# MCU.net
KiCad netlist of a schematic drawn in Altium Designer
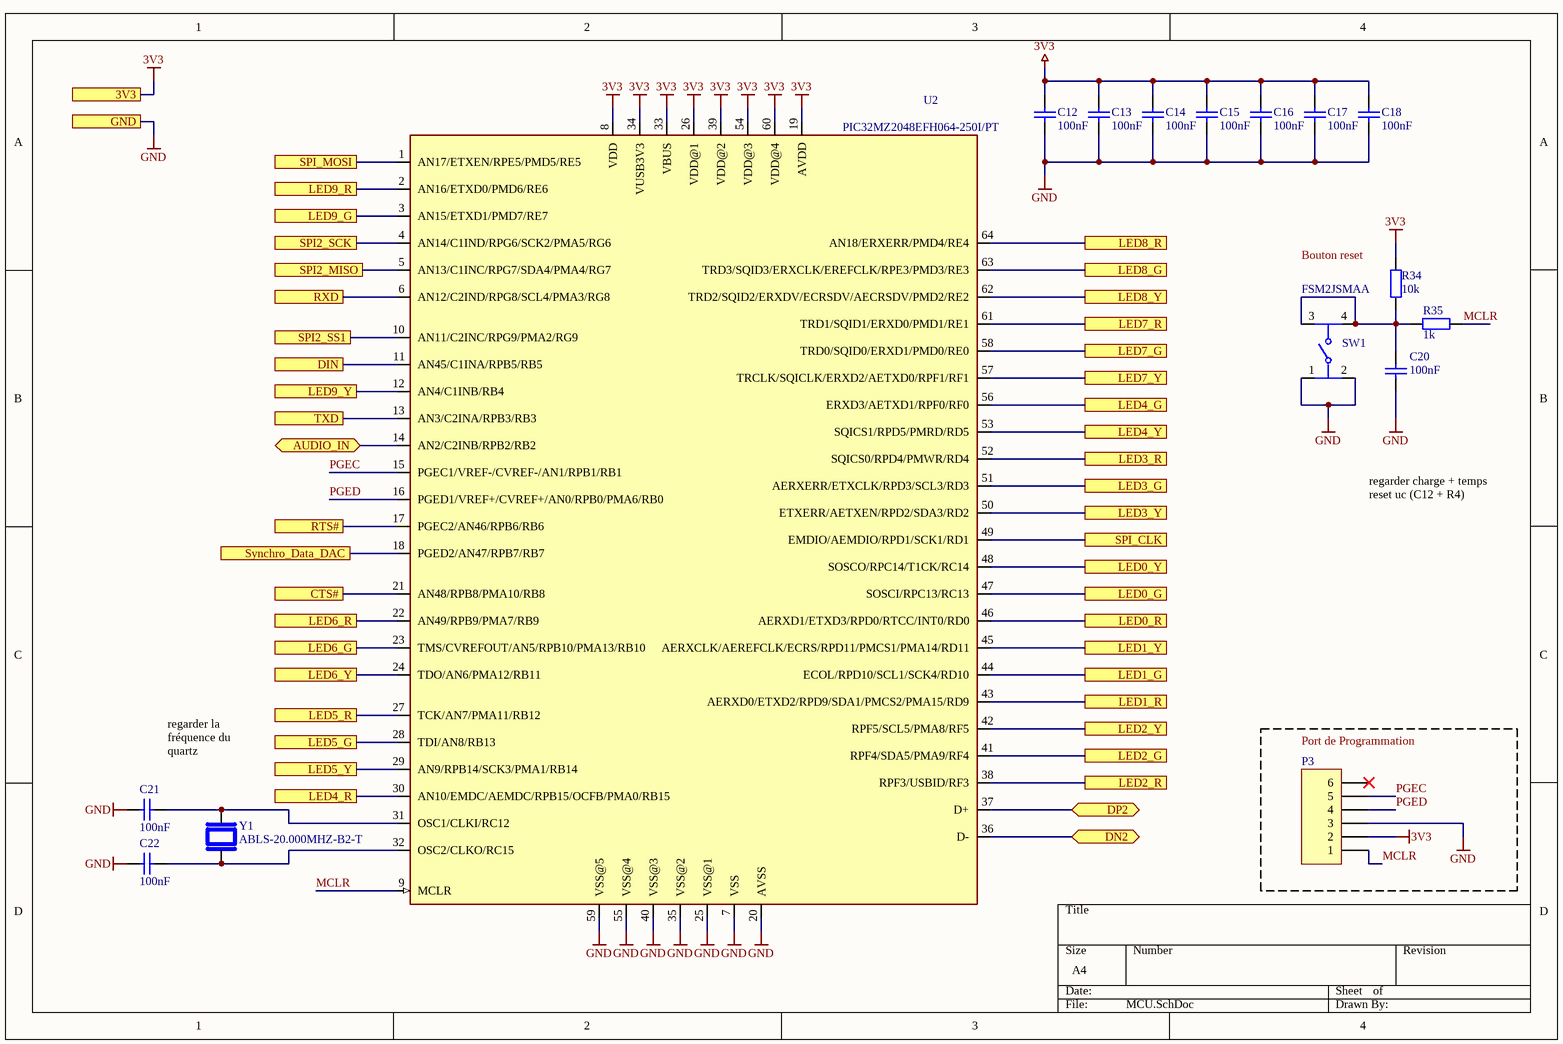
[diagram p0: MCU.SchDoc]

(export (version "E")
  (design (tool "Eeschema 10.0.6"))
  (components
    (comp (ref "C12")
      (value "100nF")
      (footprint "C0805")
      (description "Capacitor")
      (fields (field (name "PUBLISHER") "Altium Limited"))
      (libsource (lib "Miscellaneous Devices") (part "Cap"))
    )
    (comp (ref "C13")
      (value "100nF")
      (footprint "C0805")
      (description "Capacitor")
      (fields (field (name "PUBLISHER") "Altium Limited"))
      (libsource (lib "Miscellaneous Devices") (part "Cap"))
    )
    (comp (ref "C14")
      (value "100nF")
      (footprint "C0805")
      (description "Capacitor")
      (fields (field (name "PUBLISHER") "Altium Limited"))
      (libsource (lib "Miscellaneous Devices") (part "Cap"))
    )
    (comp (ref "C15")
      (value "100nF")
      (footprint "C0805")
      (description "Capacitor")
      (fields (field (name "PUBLISHER") "Altium Limited"))
      (libsource (lib "Miscellaneous Devices") (part "Cap"))
    )
    (comp (ref "C16")
      (value "100nF")
      (footprint "C0805")
      (description "Capacitor")
      (fields (field (name "PUBLISHER") "Altium Limited"))
      (libsource (lib "Miscellaneous Devices") (part "Cap"))
    )
    (comp (ref "C17")
      (value "100nF")
      (footprint "C0805")
      (description "Capacitor")
      (fields (field (name "PUBLISHER") "Altium Limited"))
      (libsource (lib "Miscellaneous Devices") (part "Cap"))
    )
    (comp (ref "C18")
      (value "100nF")
      (footprint "C0805")
      (description "Capacitor")
      (fields (field (name "PUBLISHER") "Altium Limited"))
      (libsource (lib "Miscellaneous Devices") (part "Cap"))
    )
    (comp (ref "C20")
      (value "100nF")
      (footprint "C0805")
      (description "10nf")
      (fields (field (name "PUBLISHER") "Altium Limited"))
      (libsource (lib "Miscellaneous Devices") (part "Cap"))
    )
    (comp (ref "C21")
      (value "100nF")
      (footprint "C0805")
      (description "10nf")
      (fields (field (name "PUBLISHER") "Altium Limited"))
      (libsource (lib "Miscellaneous Devices") (part "Cap"))
    )
    (comp (ref "C22")
      (value "100nF")
      (footprint "C0805")
      (description "10nf")
      (fields (field (name "PUBLISHER") "Altium Limited"))
      (libsource (lib "Miscellaneous Devices") (part "Cap"))
    )
    (comp (ref "P3")
      (value "76384-406LF")
      (footprint "HDR1X6")
      (description "Header, 6-Pin")
      (fields (field (name "PUBLISHER") "Altium Limited"))
      (libsource (lib "Miscellaneous Connectors") (part "Header 6"))
    )
    (comp (ref "R34")
      (value "10k")
      (footprint "RESC2012X06M")
      (description "Resistor")
      (fields (field (name "PUBLISHER") "Altium Limited"))
      (libsource (lib "") (part "Res2_1"))
    )
    (comp (ref "R35")
      (value "1k")
      (footprint "RESC2012X06M")
      (description "Resistor")
      (fields (field (name "PUBLISHER") "Altium Limited"))
      (libsource (lib "Miscellaneous Devices") (part "Res2"))
    )
    (comp (ref "SW1")
      (value "FSM2JSMAA")
      (footprint "FP-FSM2JSMAA-MFG")
      (description "SWITCH TACTILE SPST-NO 0.05A 24V")
      (fields
        (field (name "MANUFACTURER") "TE Connectivity")
        (field (name "OCTOPART") "https://octopart.com/fsm2jsmaa-te+connectivity-41720620")
      )
      (libsource (lib "Altium Content Vault") (part "b8895f3f4cefb76e1819d2863dba89b"))
    )
    (comp (ref "U2")
      (value "PIC32MZ2048EFH064-250I/PT")
      (footprint "QFP50P1200X1200X120-64N")
      (description "MIPS32Â® M-Class PICÂ® 32MZ Microcontroller IC 32-Bit 250MHz 2MB _2M x 8_ FLASH 64-TQFP _10x10_")
      (fields
        (field (name "MF") "Microchip")
        (field (name "DIGI-KEY_PART_NUMBER") "PIC32MZ2048EFH064-250I/PT-ND")
      )
      (libsource (lib "2225B_VumetreFrequenciel") (part "PIC32MZ2048EFH064-250I/PT"))
    )
    (comp (ref "Y1")
      (value "ABLS-20.000MHZ-B2-T")
      (footprint "XTAL_ABLS-20.000MHZ-B2-T")
      (description "HC/49US (AT49) SMD LOW PROFILE CRYSTAL")
      (fields (field (name "MF") "Abracon LLC"))
      (libsource (lib "2225B_VumetreFrequenciel") (part "ABLS-20.000MHZ-B2-T"))
    )
  )
  (nets
    (net (code "1") (name "/AUDIO_IN") (class "Default")
      (node (ref "U2") (pin "14") (pinfunction "AN2/C2INB/RPB2/RB2_14") (pintype "passive"))
    )
    (net (code "2") (name "/CTS#") (class "Default")
      (node (ref "U2") (pin "21") (pinfunction "AN48/RPB8/PMA10/RB8_21") (pintype "passive"))
    )
    (net (code "3") (name "/DIN") (class "Default")
      (node (ref "U2") (pin "11") (pinfunction "AN45/C1INA/RPB5/RB5_11") (pintype "passive"))
    )
    (net (code "4") (name "/DN2") (class "Default")
      (node (ref "U2") (pin "36") (pinfunction "D-_36") (pintype "passive"))
    )
    (net (code "5") (name "/DP2") (class "Default")
      (node (ref "U2") (pin "37") (pinfunction "D+_37") (pintype "passive"))
    )
    (net (code "6") (name "/LED0_G") (class "Default")
      (node (ref "U2") (pin "47") (pinfunction "SOSCI/RPC13/RC13_47") (pintype "passive"))
    )
    (net (code "7") (name "/LED0_R") (class "Default")
      (node (ref "U2") (pin "46") (pinfunction "AERXD1/ETXD3/RPD0/RTCC/INT0/RD0_46") (pintype "passive"))
    )
    (net (code "8") (name "/LED0_Y") (class "Default")
      (node (ref "U2") (pin "48") (pinfunction "SOSCO/RPC14/T1CK/RC14_48") (pintype "passive"))
    )
    (net (code "9") (name "/LED1_G") (class "Default")
      (node (ref "U2") (pin "44") (pinfunction "ECOL/RPD10/SCL1/SCK4/RD10_44") (pintype "passive"))
    )
    (net (code "10") (name "/LED1_R") (class "Default")
      (node (ref "U2") (pin "43") (pinfunction "AERXD0/ETXD2/RPD9/SDA1/PMCS2/PMA15/RD9_43") (pintype "passive"))
    )
    (net (code "11") (name "/LED1_Y") (class "Default")
      (node (ref "U2") (pin "45") (pinfunction "AERXCLK/AEREFCLK/ECRS/RPD11/PMCS1/PMA14/RD11_45") (pintype "passive"))
    )
    (net (code "12") (name "/LED2_G") (class "Default")
      (node (ref "U2") (pin "41") (pinfunction "RPF4/SDA5/PMA9/RF4_41") (pintype "passive"))
    )
    (net (code "13") (name "/LED2_R") (class "Default")
      (node (ref "U2") (pin "38") (pinfunction "RPF3/USBID/RF3_38") (pintype "passive"))
    )
    (net (code "14") (name "/LED2_Y") (class "Default")
      (node (ref "U2") (pin "42") (pinfunction "RPF5/SCL5/PMA8/RF5_42") (pintype "passive"))
    )
    (net (code "15") (name "/LED3_G") (class "Default")
      (node (ref "U2") (pin "51") (pinfunction "AERXERR/ETXCLK/RPD3/SCL3/RD3_51") (pintype "passive"))
    )
    (net (code "16") (name "/LED3_R") (class "Default")
      (node (ref "U2") (pin "52") (pinfunction "SQICS0/RPD4/PMWR/RD4_52") (pintype "passive"))
    )
    (net (code "17") (name "/LED3_Y") (class "Default")
      (node (ref "U2") (pin "50") (pinfunction "ETXERR/AETXEN/RPD2/SDA3/RD2_50") (pintype "passive"))
    )
    (net (code "18") (name "/LED4_G") (class "Default")
      (node (ref "U2") (pin "56") (pinfunction "ERXD3/AETXD1/RPF0/RF0_56") (pintype "passive"))
    )
    (net (code "19") (name "/LED4_R") (class "Default")
      (node (ref "U2") (pin "30") (pinfunction "AN10/EMDC/AEMDC/RPB15/OCFB/PMA0/RB15_30") (pintype "passive"))
    )
    (net (code "20") (name "/LED4_Y") (class "Default")
      (node (ref "U2") (pin "53") (pinfunction "SQICS1/RPD5/PMRD/RD5_53") (pintype "passive"))
    )
    (net (code "21") (name "/LED5_G") (class "Default")
      (node (ref "U2") (pin "28") (pinfunction "TDI/AN8/RB13_28") (pintype "passive"))
    )
    (net (code "22") (name "/LED5_R") (class "Default")
      (node (ref "U2") (pin "27") (pinfunction "TCK/AN7/PMA11/RB12_27") (pintype "passive"))
    )
    (net (code "23") (name "/LED5_Y") (class "Default")
      (node (ref "U2") (pin "29") (pinfunction "AN9/RPB14/SCK3/PMA1/RB14_29") (pintype "passive"))
    )
    (net (code "24") (name "/LED6_G") (class "Default")
      (node (ref "U2") (pin "23") (pinfunction "TMS/CVREFOUT/AN5/RPB10/PMA13/RB10_23") (pintype "passive"))
    )
    (net (code "25") (name "/LED6_R") (class "Default")
      (node (ref "U2") (pin "22") (pinfunction "AN49/RPB9/PMA7/RB9_22") (pintype "passive"))
    )
    (net (code "26") (name "/LED6_Y") (class "Default")
      (node (ref "U2") (pin "24") (pinfunction "TDO/AN6/PMA12/RB11_24") (pintype "passive"))
    )
    (net (code "27") (name "/LED7_G") (class "Default")
      (node (ref "U2") (pin "58") (pinfunction "TRD0/SQID0/ERXD1/PMD0/RE0_58") (pintype "passive"))
    )
    (net (code "28") (name "/LED7_R") (class "Default")
      (node (ref "U2") (pin "61") (pinfunction "TRD1/SQID1/ERXD0/PMD1/RE1_61") (pintype "passive"))
    )
    (net (code "29") (name "/LED7_Y") (class "Default")
      (node (ref "U2") (pin "57") (pinfunction "TRCLK/SQICLK/ERXD2/AETXD0/RPF1/RF1_57") (pintype "passive"))
    )
    (net (code "30") (name "/LED8_G") (class "Default")
      (node (ref "U2") (pin "63") (pinfunction "TRD3/SQID3/ERXCLK/EREFCLK/RPE3/PMD3/RE3_63") (pintype "passive"))
    )
    (net (code "31") (name "/LED8_R") (class "Default")
      (node (ref "U2") (pin "64") (pinfunction "AN18/ERXERR/PMD4/RE4_64") (pintype "passive"))
    )
    (net (code "32") (name "/LED8_Y") (class "Default")
      (node (ref "U2") (pin "62") (pinfunction "TRD2/SQID2/ERXDV/ECRSDV/AECRSDV/PMD2/RE2_62") (pintype "passive"))
    )
    (net (code "33") (name "/LED9_G") (class "Default")
      (node (ref "U2") (pin "3") (pinfunction "AN15/ETXD1/PMD7/RE7_3") (pintype "passive"))
    )
    (net (code "34") (name "/LED9_R") (class "Default")
      (node (ref "U2") (pin "2") (pinfunction "AN16/ETXD0/PMD6/RE6_2") (pintype "passive"))
    )
    (net (code "35") (name "/LED9_Y") (class "Default")
      (node (ref "U2") (pin "12") (pinfunction "AN4/C1INB/RB4_12") (pintype "passive"))
    )
    (net (code "36") (name "/MCLR") (class "Default")
      (node (ref "P3") (pin "1") (pinfunction "1_1") (pintype "passive"))
      (node (ref "R35") (pin "1") (pinfunction "1_1") (pintype "passive"))
      (node (ref "U2") (pin "9") (pinfunction "MCLR_9") (pintype "input"))
    )
    (net (code "37") (name "/PGEC") (class "Default")
      (node (ref "P3") (pin "5") (pinfunction "5_5") (pintype "passive"))
      (node (ref "U2") (pin "15") (pinfunction "PGEC1/VREF-/CVREF-/AN1/RPB1/RB1_15") (pintype "passive"))
    )
    (net (code "38") (name "/PGED") (class "Default")
      (node (ref "P3") (pin "4") (pinfunction "4_4") (pintype "passive"))
      (node (ref "U2") (pin "16") (pinfunction "PGED1/VREF+/CVREF+/AN0/RPB0/PMA6/RB0_16") (pintype "passive"))
    )
    (net (code "39") (name "/RTS#") (class "Default")
      (node (ref "U2") (pin "17") (pinfunction "PGEC2/AN46/RPB6/RB6_17") (pintype "passive"))
    )
    (net (code "40") (name "/RXD") (class "Default")
      (node (ref "U2") (pin "6") (pinfunction "AN12/C2IND/RPG8/SCL4/PMA3/RG8_6") (pintype "passive"))
    )
    (net (code "41") (name "/SPI2_MISO") (class "Default")
      (node (ref "U2") (pin "5") (pinfunction "AN13/C1INC/RPG7/SDA4/PMA4/RG7_5") (pintype "passive"))
    )
    (net (code "42") (name "/SPI2_SCK") (class "Default")
      (node (ref "U2") (pin "4") (pinfunction "AN14/C1IND/RPG6/SCK2/PMA5/RG6_4") (pintype "passive"))
    )
    (net (code "43") (name "/SPI2_SS1") (class "Default")
      (node (ref "U2") (pin "10") (pinfunction "AN11/C2INC/RPG9/PMA2/RG9_10") (pintype "passive"))
    )
    (net (code "44") (name "/SPI_CLK") (class "Default")
      (node (ref "U2") (pin "49") (pinfunction "EMDIO/AEMDIO/RPD1/SCK1/RD1_49") (pintype "passive"))
    )
    (net (code "45") (name "/SPI_MOSI") (class "Default")
      (node (ref "U2") (pin "1") (pinfunction "AN17/ETXEN/RPE5/PMD5/RE5_1") (pintype "passive"))
    )
    (net (code "46") (name "/Synchro_Data_DAC") (class "Default")
      (node (ref "U2") (pin "18") (pinfunction "PGED2/AN47/RPB7/RB7_18") (pintype "passive"))
    )
    (net (code "47") (name "/TXD") (class "Default")
      (node (ref "U2") (pin "13") (pinfunction "AN3/C2INA/RPB3/RB3_13") (pintype "passive"))
    )
    (net (code "48") (name "3V3") (class "Default")
      (node (ref "C12") (pin "1") (pinfunction "1_1") (pintype "passive"))
      (node (ref "C13") (pin "1") (pinfunction "1_1") (pintype "passive"))
      (node (ref "C14") (pin "1") (pinfunction "1_1") (pintype "passive"))
      (node (ref "C15") (pin "1") (pinfunction "1_1") (pintype "passive"))
      (node (ref "C16") (pin "1") (pinfunction "1_1") (pintype "passive"))
      (node (ref "C17") (pin "1") (pinfunction "1_1") (pintype "passive"))
      (node (ref "C18") (pin "1") (pinfunction "1_1") (pintype "passive"))
      (node (ref "P3") (pin "2") (pinfunction "2_2") (pintype "passive"))
      (node (ref "R34") (pin "1") (pinfunction "1_1") (pintype "passive"))
      (node (ref "U2") (pin "19") (pinfunction "AVDD_19") (pintype "power_in"))
      (node (ref "U2") (pin "26") (pinfunction "VDD@1_26") (pintype "power_in"))
      (node (ref "U2") (pin "33") (pinfunction "VBUS_33") (pintype "power_in"))
      (node (ref "U2") (pin "34") (pinfunction "VUSB3V3_34") (pintype "power_in"))
      (node (ref "U2") (pin "39") (pinfunction "VDD@2_39") (pintype "power_in"))
      (node (ref "U2") (pin "54") (pinfunction "VDD@3_54") (pintype "power_in"))
      (node (ref "U2") (pin "60") (pinfunction "VDD@4_60") (pintype "power_in"))
      (node (ref "U2") (pin "8") (pinfunction "VDD_8") (pintype "power_in"))
    )
    (net (code "49") (name "GND") (class "Default")
      (node (ref "C12") (pin "2") (pinfunction "2_2") (pintype "passive"))
      (node (ref "C13") (pin "2") (pinfunction "2_2") (pintype "passive"))
      (node (ref "C14") (pin "2") (pinfunction "2_2") (pintype "passive"))
      (node (ref "C15") (pin "2") (pinfunction "2_2") (pintype "passive"))
      (node (ref "C16") (pin "2") (pinfunction "2_2") (pintype "passive"))
      (node (ref "C17") (pin "2") (pinfunction "2_2") (pintype "passive"))
      (node (ref "C18") (pin "2") (pinfunction "2_2") (pintype "passive"))
      (node (ref "C20") (pin "1") (pinfunction "1_1") (pintype "passive"))
      (node (ref "C21") (pin "2") (pinfunction "2_2") (pintype "passive"))
      (node (ref "C22") (pin "2") (pinfunction "2_2") (pintype "passive"))
      (node (ref "P3") (pin "3") (pinfunction "3_3") (pintype "passive"))
      (node (ref "SW1") (pin "1") (pinfunction "1_1") (pintype "passive"))
      (node (ref "SW1") (pin "2") (pinfunction "2_2") (pintype "passive"))
      (node (ref "U2") (pin "20") (pinfunction "AVSS_20") (pintype "power_in"))
      (node (ref "U2") (pin "25") (pinfunction "VSS@1_25") (pintype "power_in"))
      (node (ref "U2") (pin "35") (pinfunction "VSS@2_35") (pintype "power_in"))
      (node (ref "U2") (pin "40") (pinfunction "VSS@3_40") (pintype "power_in"))
      (node (ref "U2") (pin "55") (pinfunction "VSS@4_55") (pintype "power_in"))
      (node (ref "U2") (pin "59") (pinfunction "VSS@5_59") (pintype "power_in"))
      (node (ref "U2") (pin "7") (pinfunction "VSS_7") (pintype "power_in"))
    )
    (net (code "50") (name "Net-(C20-Pad2)") (class "Default")
      (node (ref "C20") (pin "2") (pinfunction "2_2") (pintype "passive"))
      (node (ref "R34") (pin "2") (pinfunction "2_2") (pintype "passive"))
      (node (ref "R35") (pin "2") (pinfunction "2_2") (pintype "passive"))
      (node (ref "SW1") (pin "3") (pinfunction "3_3") (pintype "passive"))
      (node (ref "SW1") (pin "4") (pinfunction "4_4") (pintype "passive"))
    )
    (net (code "51") (name "Net-(U2-OSC1{slash}CLKI{slash}RC12)") (class "Default")
      (node (ref "C21") (pin "1") (pinfunction "1_1") (pintype "passive"))
      (node (ref "U2") (pin "31") (pinfunction "OSC1/CLKI/RC12_31") (pintype "passive"))
      (node (ref "Y1") (pin "2") (pinfunction "2_2") (pintype "passive"))
    )
    (net (code "52") (name "Net-(U2-OSC2{slash}CLKO{slash}RC15)") (class "Default")
      (node (ref "C22") (pin "1") (pinfunction "1_1") (pintype "passive"))
      (node (ref "U2") (pin "32") (pinfunction "OSC2/CLKO/RC15_32") (pintype "passive"))
      (node (ref "Y1") (pin "1") (pinfunction "1_1") (pintype "passive"))
    )
    (net (code "53") (name "unconnected-(P3-Pad6)") (class "Default")
      (node (ref "P3") (pin "6") (pinfunction "6_6") (pintype "passive+no_connect"))
    )
  )
)
